# recall_mcu_2L_v0_1.net
KiCad netlist of a schematic drawn in Altium Designer
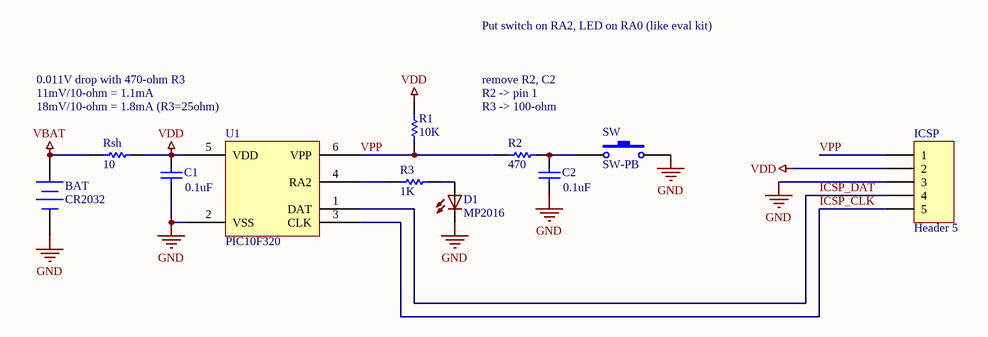
[diagram p0: recall_mcu_2L_v0_1.SchDoc]

(export (version "E")
  (design (tool "Eeschema 10.0.6"))
  (components
    (comp (ref "BAT")
      (value "CR2032")
      (footprint "BAT-HLD-001-THM")
      (fields (field (name "PUBLISHER") "Altium Limited"))
      (libsource (lib "recall") (part "Battery"))
    )
    (comp (ref "C1")
      (value "0.1uF")
      (footprint "CAP_0402R")
      (description "Capacitor")
      (fields (field (name "Comment") "CAP") (field (name "PUBLISHER") "Altium Limited"))
      (libsource (lib "recall") (part "CAP"))
    )
    (comp (ref "C2")
      (value "0.1uF")
      (footprint "CAP_0402R")
      (description "Capacitor")
      (fields (field (name "Comment") "CAP") (field (name "PUBLISHER") "Altium Limited"))
      (libsource (lib "recall") (part "CAP"))
    )
    (comp (ref "D1")
      (value "MP2016")
      (footprint "MP2016_centered")
      (description "MP2016 White LED")
      (libsource (lib "recall") (part "MP2016"))
    )
    (comp (ref "ICSP")
      (value "Header 5")
      (footprint "HDR1X5_ICSP")
      (description "Header, 5-Pin")
      (fields (field (name "PUBLISHER") "Altium Limited"))
      (libsource (lib "recall") (part "Header 5"))
    )
    (comp (ref "R1")
      (value "10K")
      (footprint "RES_0402")
      (description "Resistor")
      (fields (field (name "Comment") "RES") (field (name "PUBLISHER") "Altium Limited"))
      (libsource (lib "recall") (part "RES"))
    )
    (comp (ref "R2")
      (value "470")
      (footprint "RES_0402")
      (description "Resistor")
      (fields (field (name "Comment") "RES") (field (name "PUBLISHER") "Altium Limited"))
      (libsource (lib "recall") (part "RES"))
    )
    (comp (ref "R3")
      (value "1K")
      (footprint "RES_0402")
      (description "Resistor")
      (fields (field (name "Comment") "RES") (field (name "PUBLISHER") "Altium Limited"))
      (libsource (lib "recall") (part "RES"))
    )
    (comp (ref "Rsh")
      (value "10")
      (footprint "RES_0402")
      (description "Resistor")
      (fields (field (name "Comment") "RES") (field (name "PUBLISHER") "Altium Limited"))
      (libsource (lib "recall") (part "RES"))
    )
    (comp (ref "SW")
      (value "SW-PB")
      (footprint "TRELLIS_1x1_2L")
      (description "Translucent Conductive Silicone Elastomer Switch")
      (fields (field (name "PUBLISHER") "Altium Limited"))
      (libsource (lib "recall") (part "SW-PB"))
    )
    (comp (ref "U1")
      (value "PIC10F320")
      (footprint "SOT-23-6")
      (description "6-Pin Flash-Based, 8-Bit Microcontroller")
      (libsource (lib "recall") (part "PIC10F320"))
    )
  )
  (nets
    (net (code "1") (name "/ICSP_CLK") (class "Default")
      (node (ref "ICSP") (pin "5") (pinfunction "5_5") (pintype "passive"))
      (node (ref "U1") (pin "3") (pinfunction "CLK_3") (pintype "passive"))
    )
    (net (code "2") (name "/ICSP_DAT") (class "Default")
      (node (ref "ICSP") (pin "4") (pinfunction "4_4") (pintype "passive"))
      (node (ref "U1") (pin "1") (pinfunction "DAT_1") (pintype "passive"))
    )
    (net (code "3") (name "/VPP") (class "Default")
      (node (ref "ICSP") (pin "1") (pinfunction "1_1") (pintype "passive"))
      (node (ref "R1") (pin "1") (pinfunction "1_1") (pintype "passive"))
      (node (ref "R2") (pin "2") (pinfunction "2_2") (pintype "passive"))
      (node (ref "U1") (pin "6") (pinfunction "VPP_6") (pintype "passive"))
    )
    (net (code "4") (name "GND") (class "Default")
      (node (ref "BAT") (pin "2") (pinfunction "-_2") (pintype "passive"))
      (node (ref "C1") (pin "1") (pinfunction "1_1") (pintype "passive"))
      (node (ref "C2") (pin "1") (pinfunction "1_1") (pintype "passive"))
      (node (ref "D1") (pin "C") (pinfunction "C_C") (pintype "passive"))
      (node (ref "ICSP") (pin "3") (pinfunction "3_3") (pintype "passive"))
      (node (ref "SW") (pin "2") (pinfunction "2_2") (pintype "passive"))
      (node (ref "U1") (pin "2") (pinfunction "VSS_2") (pintype "passive"))
    )
    (net (code "5") (name "Net-(C2-Pad2)") (class "Default")
      (node (ref "C2") (pin "2") (pinfunction "2_2") (pintype "passive"))
      (node (ref "R2") (pin "1") (pinfunction "1_1") (pintype "passive"))
      (node (ref "SW") (pin "1") (pinfunction "1_1") (pintype "passive"))
    )
    (net (code "6") (name "Net-(D1-PadA)") (class "Default")
      (node (ref "D1") (pin "A") (pinfunction "A_A") (pintype "passive"))
      (node (ref "R3") (pin "1") (pinfunction "1_1") (pintype "passive"))
    )
    (net (code "7") (name "Net-(U1-RA2)") (class "Default")
      (node (ref "R3") (pin "2") (pinfunction "2_2") (pintype "passive"))
      (node (ref "U1") (pin "4") (pinfunction "RA2_4") (pintype "passive"))
    )
    (net (code "8") (name "VBAT") (class "Default")
      (node (ref "BAT") (pin "1") (pinfunction "+_1") (pintype "passive"))
      (node (ref "Rsh") (pin "1") (pinfunction "1_1") (pintype "passive"))
    )
    (net (code "9") (name "VDD") (class "Default")
      (node (ref "C1") (pin "2") (pinfunction "2_2") (pintype "passive"))
      (node (ref "ICSP") (pin "2") (pinfunction "2_2") (pintype "passive"))
      (node (ref "R1") (pin "2") (pinfunction "2_2") (pintype "passive"))
      (node (ref "Rsh") (pin "2") (pinfunction "2_2") (pintype "passive"))
      (node (ref "U1") (pin "5") (pinfunction "VDD_5") (pintype "passive"))
    )
  )
)
